# project.net
KiCad netlist of a schematic drawn in EAGLE
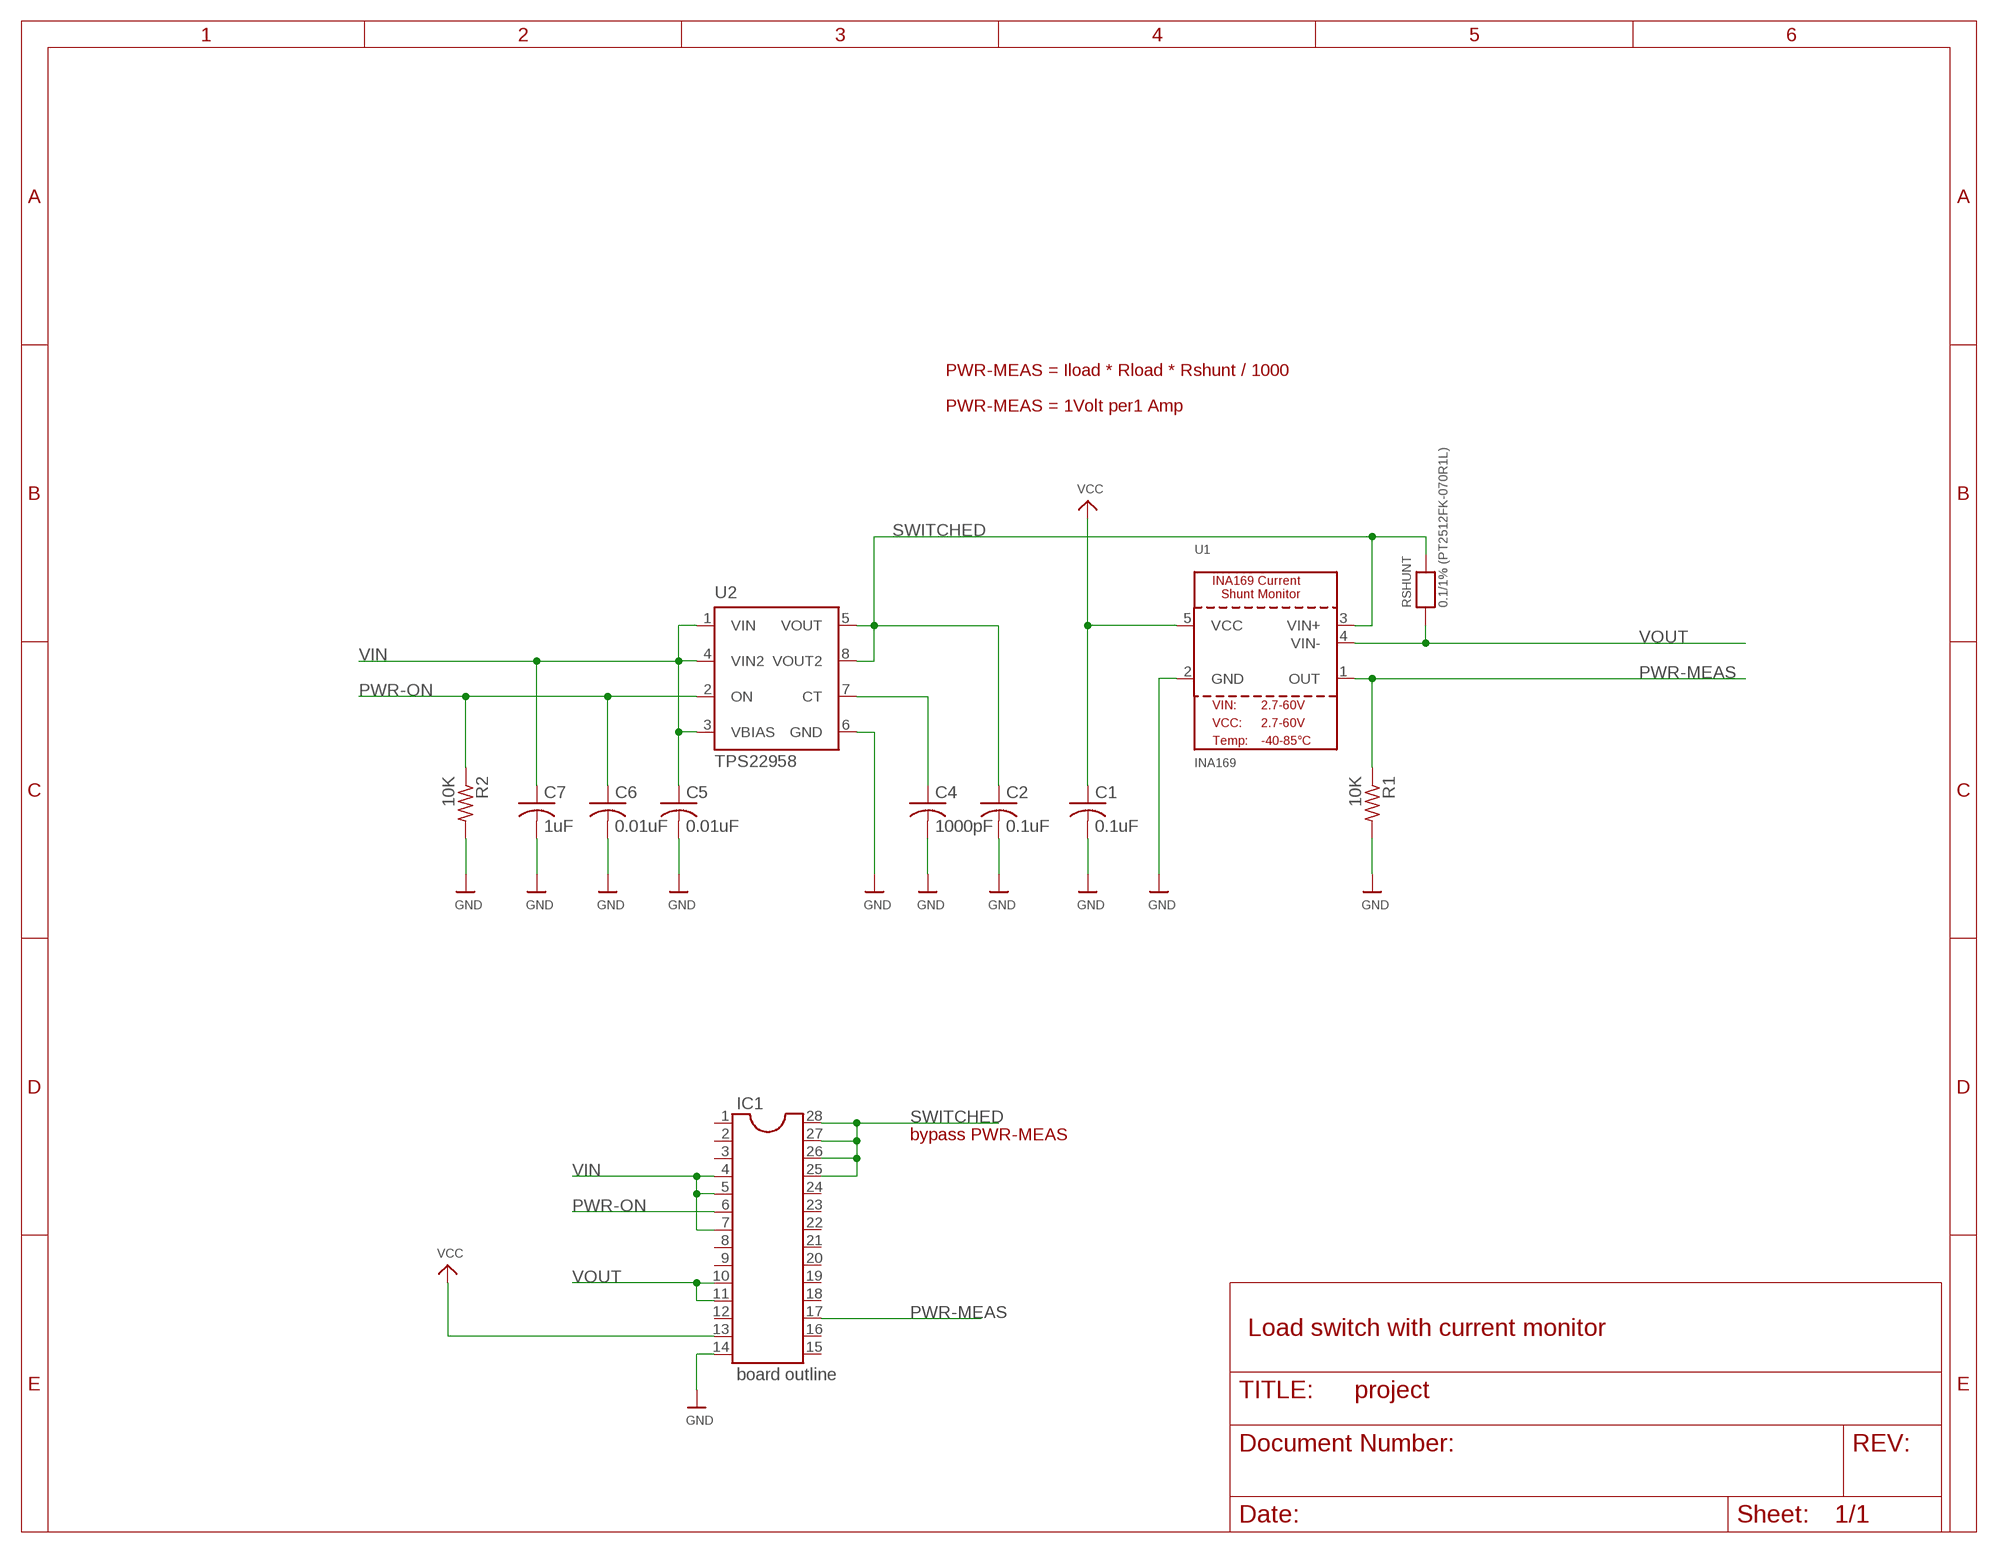
[diagram p0: schematic, sheet 1]

(export (version "E")
  (design (tool "Eeschema 10.0.6"))
  (components
    (comp (ref "C1")
      (value "0.1uF")
      (footprint "eagle-import:C1206K")
      (libsource (lib "eagle-import") (part "C-USC1206K"))
    )
    (comp (ref "C2")
      (value "0.1uF")
      (footprint "eagle-import:C1206K")
      (libsource (lib "eagle-import") (part "C-USC1206K"))
    )
    (comp (ref "C4")
      (value "1000pF")
      (footprint "eagle-import:C1206K")
      (libsource (lib "eagle-import") (part "C-USC1206K"))
    )
    (comp (ref "C5")
      (value "0.01uF")
      (footprint "eagle-import:C1206K")
      (libsource (lib "eagle-import") (part "C-USC1206K"))
    )
    (comp (ref "C6")
      (value "0.01uF")
      (footprint "eagle-import:C1206K")
      (libsource (lib "eagle-import") (part "C-USC1206K"))
    )
    (comp (ref "C7")
      (value "1uF")
      (footprint "eagle-import:C1206K")
      (libsource (lib "eagle-import") (part "C-USC1206K"))
    )
    (comp (ref "IC1")
      (value "board outline")
      (footprint "eagle-import:DIL28-6")
      (libsource (lib "eagle-import") (part "DIL28"))
    )
    (comp (ref "R1")
      (value "10K")
      (footprint "eagle-import:M1206")
      (libsource (lib "eagle-import") (part "R-US_M1206"))
    )
    (comp (ref "R2")
      (value "10K")
      (footprint "eagle-import:M1206")
      (libsource (lib "eagle-import") (part "R-US_M1206"))
    )
    (comp (ref "RSHUNT")
      (value "0.1/1% (PT2512FK-070R1L)")
      (footprint "eagle-import:2512")
      (libsource (lib "eagle-import") (part "RESISTOR2512"))
    )
    (comp (ref "U1")
      (value "INA169")
      (footprint "eagle-import:SOT23-5")
      (libsource (lib "eagle-import") (part "INA169"))
    )
    (comp (ref "U2")
      (value "TPS22958")
      (footprint "eagle-import:S-PDSO-G08")
      (libsource (lib "eagle-import") (part "TPS22958"))
    )
  )
  (nets
    (net (code "1") (name "/PWR-MEAS") (class "Default")
      (node (ref "IC1") (pin "17") (pinfunction "17_17") (pintype "passive"))
      (node (ref "R1") (pin "1") (pinfunction "1_1") (pintype "passive"))
      (node (ref "U1") (pin "1") (pinfunction "OUT_1") (pintype "output"))
    )
    (net (code "2") (name "/PWR-ON") (class "Default")
      (node (ref "C6") (pin "1") (pinfunction "1_1") (pintype "passive"))
      (node (ref "IC1") (pin "6") (pinfunction "6_6") (pintype "passive"))
      (node (ref "R2") (pin "1") (pinfunction "1_1") (pintype "passive"))
      (node (ref "U2") (pin "2") (pinfunction "ON_2") (pintype "input"))
    )
    (net (code "3") (name "/SWITCHED") (class "Default")
      (node (ref "C2") (pin "1") (pinfunction "1_1") (pintype "passive"))
      (node (ref "IC1") (pin "25") (pinfunction "25_25") (pintype "passive"))
      (node (ref "IC1") (pin "26") (pinfunction "26_26") (pintype "passive"))
      (node (ref "IC1") (pin "27") (pinfunction "27_27") (pintype "passive"))
      (node (ref "IC1") (pin "28") (pinfunction "28_28") (pintype "passive"))
      (node (ref "RSHUNT") (pin "2") (pinfunction "2_2") (pintype "passive"))
      (node (ref "U1") (pin "3") (pinfunction "VIN+_3") (pintype "bidirectional"))
      (node (ref "U2") (pin "5") (pinfunction "VOUT_5") (pintype "input"))
      (node (ref "U2") (pin "8") (pinfunction "VOUT2_8") (pintype "output"))
    )
    (net (code "4") (name "/VIN") (class "Default")
      (node (ref "C5") (pin "1") (pinfunction "1_1") (pintype "passive"))
      (node (ref "C7") (pin "1") (pinfunction "1_1") (pintype "passive"))
      (node (ref "IC1") (pin "4") (pinfunction "4_4") (pintype "passive"))
      (node (ref "IC1") (pin "5") (pinfunction "5_5") (pintype "passive"))
      (node (ref "IC1") (pin "7") (pinfunction "7_7") (pintype "passive"))
      (node (ref "U2") (pin "1") (pinfunction "VIN_1") (pintype "input"))
      (node (ref "U2") (pin "3") (pinfunction "VBIAS_3") (pintype "power_in"))
      (node (ref "U2") (pin "4") (pinfunction "VIN2_4") (pintype "passive"))
    )
    (net (code "5") (name "/VOUT") (class "Default")
      (node (ref "IC1") (pin "10") (pinfunction "10_10") (pintype "passive"))
      (node (ref "IC1") (pin "11") (pinfunction "11_11") (pintype "passive"))
      (node (ref "RSHUNT") (pin "1") (pinfunction "1_1") (pintype "passive"))
      (node (ref "U1") (pin "4") (pinfunction "VIN-_4") (pintype "bidirectional"))
    )
    (net (code "6") (name "GND") (class "Default")
      (node (ref "C1") (pin "2") (pinfunction "2_2") (pintype "passive"))
      (node (ref "C2") (pin "2") (pinfunction "2_2") (pintype "passive"))
      (node (ref "C4") (pin "2") (pinfunction "2_2") (pintype "passive"))
      (node (ref "C5") (pin "2") (pinfunction "2_2") (pintype "passive"))
      (node (ref "C6") (pin "2") (pinfunction "2_2") (pintype "passive"))
      (node (ref "C7") (pin "2") (pinfunction "2_2") (pintype "passive"))
      (node (ref "IC1") (pin "14") (pinfunction "14_14") (pintype "passive"))
      (node (ref "R1") (pin "2") (pinfunction "2_2") (pintype "passive"))
      (node (ref "R2") (pin "2") (pinfunction "2_2") (pintype "passive"))
      (node (ref "U1") (pin "2") (pinfunction "GND_2") (pintype "power_in"))
      (node (ref "U2") (pin "6") (pinfunction "GND_6") (pintype "input"))
    )
    (net (code "7") (name "Net-(U2-CT)") (class "Default")
      (node (ref "C4") (pin "1") (pinfunction "1_1") (pintype "passive"))
      (node (ref "U2") (pin "7") (pinfunction "CT_7") (pintype "input"))
    )
    (net (code "8") (name "VCC") (class "Default")
      (node (ref "C1") (pin "1") (pinfunction "1_1") (pintype "passive"))
      (node (ref "IC1") (pin "13") (pinfunction "13_13") (pintype "passive"))
      (node (ref "U1") (pin "5") (pinfunction "VCC_5") (pintype "power_in"))
    )
    (net (code "9") (name "unconnected-(IC1-Pad1)") (class "Default")
      (node (ref "IC1") (pin "1") (pinfunction "1_1") (pintype "passive"))
    )
    (net (code "10") (name "unconnected-(IC1-Pad2)") (class "Default")
      (node (ref "IC1") (pin "2") (pinfunction "2_2") (pintype "passive"))
    )
    (net (code "11") (name "unconnected-(IC1-Pad3)") (class "Default")
      (node (ref "IC1") (pin "3") (pinfunction "3_3") (pintype "passive"))
    )
    (net (code "12") (name "unconnected-(IC1-Pad8)") (class "Default")
      (node (ref "IC1") (pin "8") (pinfunction "8_8") (pintype "passive"))
    )
    (net (code "13") (name "unconnected-(IC1-Pad9)") (class "Default")
      (node (ref "IC1") (pin "9") (pinfunction "9_9") (pintype "passive"))
    )
    (net (code "14") (name "unconnected-(IC1-Pad12)") (class "Default")
      (node (ref "IC1") (pin "12") (pinfunction "12_12") (pintype "passive"))
    )
    (net (code "15") (name "unconnected-(IC1-Pad15)") (class "Default")
      (node (ref "IC1") (pin "15") (pinfunction "15_15") (pintype "passive"))
    )
    (net (code "16") (name "unconnected-(IC1-Pad16)") (class "Default")
      (node (ref "IC1") (pin "16") (pinfunction "16_16") (pintype "passive"))
    )
    (net (code "17") (name "unconnected-(IC1-Pad18)") (class "Default")
      (node (ref "IC1") (pin "18") (pinfunction "18_18") (pintype "passive"))
    )
    (net (code "18") (name "unconnected-(IC1-Pad19)") (class "Default")
      (node (ref "IC1") (pin "19") (pinfunction "19_19") (pintype "passive"))
    )
    (net (code "19") (name "unconnected-(IC1-Pad20)") (class "Default")
      (node (ref "IC1") (pin "20") (pinfunction "20_20") (pintype "passive"))
    )
    (net (code "20") (name "unconnected-(IC1-Pad21)") (class "Default")
      (node (ref "IC1") (pin "21") (pinfunction "21_21") (pintype "passive"))
    )
    (net (code "21") (name "unconnected-(IC1-Pad22)") (class "Default")
      (node (ref "IC1") (pin "22") (pinfunction "22_22") (pintype "passive"))
    )
    (net (code "22") (name "unconnected-(IC1-Pad23)") (class "Default")
      (node (ref "IC1") (pin "23") (pinfunction "23_23") (pintype "passive"))
    )
    (net (code "23") (name "unconnected-(IC1-Pad24)") (class "Default")
      (node (ref "IC1") (pin "24") (pinfunction "24_24") (pintype "passive"))
    )
  )
)
